# AVR.net
KiCad netlist of a schematic drawn in Altium Designer
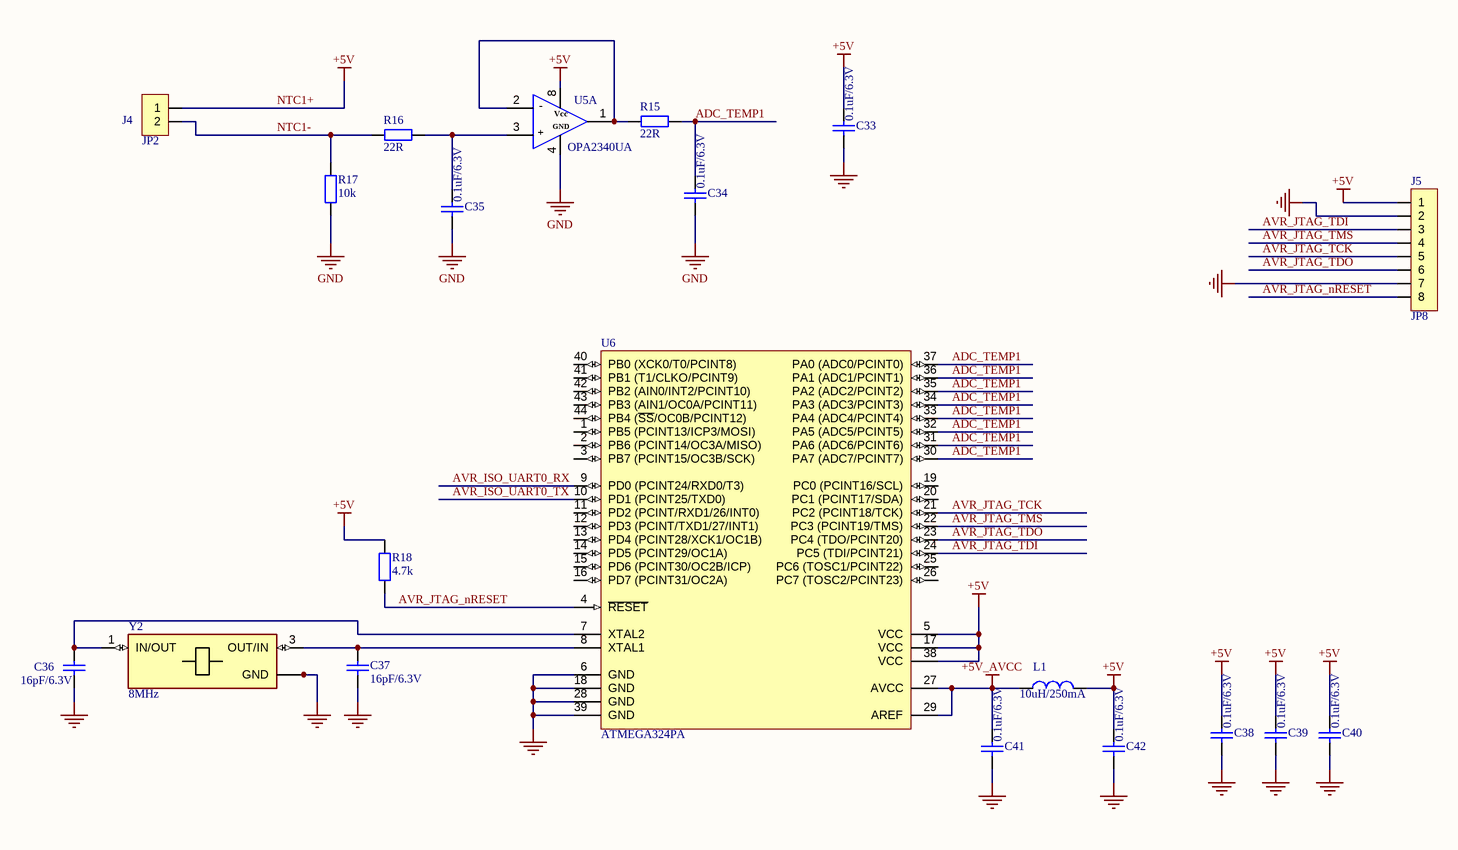
[diagram p0: AVR.SchDoc]

(export (version "E")
  (design (tool "Eeschema 10.0.6"))
  (components
    (comp (ref "C33")
      (value "0.1uF/6.3V")
      (footprint "CAP_C_1608X80")
      (description "CAPC")
      (libsource (lib "Altium_Lib_by_KhueNguyenCreator") (part "Tu 0402 33nF 10V"))
    )
    (comp (ref "C34")
      (value "0.1uF/6.3V")
      (footprint "CAP_C_1608X80")
      (description "CAPC")
      (libsource (lib "Altium_Lib_by_KhueNguyenCreator") (part "Tu 0402 33nF 10V"))
    )
    (comp (ref "C35")
      (value "0.1uF/6.3V")
      (footprint "CAP_C_1608X80")
      (description "CAPC")
      (libsource (lib "Altium_Lib_by_KhueNguyenCreator") (part "Tu 0402 33nF 10V"))
    )
    (comp (ref "C36")
      (value "16pF/6.3V")
      (footprint "CAP_C_1608X80")
      (description "CAPC")
      (libsource (lib "Altium_Lib_by_KhueNguyenCreator") (part "Tu 0402 33nF 10V"))
    )
    (comp (ref "C37")
      (value "16pF/6.3V")
      (footprint "CAP_C_1608X80")
      (description "CAPC")
      (libsource (lib "Altium_Lib_by_KhueNguyenCreator") (part "Tu 0402 33nF 10V"))
    )
    (comp (ref "C38")
      (value "0.1uF/6.3V")
      (footprint "CAP_C_1608X80")
      (description "CAPC")
      (libsource (lib "Altium_Lib_by_KhueNguyenCreator") (part "Tu 0402 33nF 10V"))
    )
    (comp (ref "C39")
      (value "0.1uF/6.3V")
      (footprint "CAP_C_1608X80")
      (description "CAPC")
      (libsource (lib "Altium_Lib_by_KhueNguyenCreator") (part "Tu 0402 33nF 10V"))
    )
    (comp (ref "C40")
      (value "0.1uF/6.3V")
      (footprint "CAP_C_1608X80")
      (description "CAPC")
      (libsource (lib "Altium_Lib_by_KhueNguyenCreator") (part "Tu 0402 33nF 10V"))
    )
    (comp (ref "C41")
      (value "0.1uF/6.3V")
      (footprint "CAP_C_1608X80")
      (description "CAPC")
      (libsource (lib "Altium_Lib_by_KhueNguyenCreator") (part "Tu 0402 33nF 10V"))
    )
    (comp (ref "C42")
      (value "0.1uF/6.3V")
      (footprint "CAP_C_1608X80")
      (description "CAPC")
      (libsource (lib "Altium_Lib_by_KhueNguyenCreator") (part "Tu 0402 33nF 10V"))
    )
    (comp (ref "J4")
      (value "JP2")
      (footprint "JP2-D1T")
      (description "WR-PHD 2.54 mm Angled Socket Header")
      (fields
        (field (name "MANUFACTURER") "Würth Elektronik eiSos GmbH")
        (field (name "PARTNO") "613002143121")
        (field (name "CREATED BY") "Karrer Zheng")
      )
      (libsource (lib "TechMT.VN_Lib") (part "JP2"))
    )
    (comp (ref "J5") (value "JP8") (footprint "JP8-C1T") (libsource (lib "obc_ver2") (part "JP8")))
    (comp (ref "L1")
      (value "10uH/250mA")
      (footprint "RES_C_1608X60")
      (fields
        (field (name "PARTNO") "78477010")
        (field (name "MANUFACTURER") "Wurth Elektronik")
        (field (name "CREATED BY") "Baojun Chen")
      )
      (libsource (lib "Sang_library") (part "L-SMD-1"))
    )
    (comp (ref "R15")
      (value "22R")
      (footprint "RES_C_1608X60")
      (description "RES")
      (libsource (lib "Altium_Lib_by_KhueNguyenCreator") (part "Tro 0603 1% 10k"))
    )
    (comp (ref "R16")
      (value "22R")
      (footprint "RES_C_1608X60")
      (description "RES")
      (libsource (lib "Altium_Lib_by_KhueNguyenCreator") (part "Tro 0603 1% 10k"))
    )
    (comp (ref "R17")
      (value "10k")
      (footprint "RES_C_1608X60")
      (description "RES")
      (libsource (lib "Altium_Lib_by_KhueNguyenCreator") (part "Tro 0603 1% 10k"))
    )
    (comp (ref "R18")
      (value "4.7k")
      (footprint "RES_C_1608X60")
      (description "RES")
      (libsource (lib "Altium_Lib_by_KhueNguyenCreator") (part "Tro 0603 1% 10k"))
    )
    (comp (ref "U5")
      (value "OPA2340UA")
      (footprint "SOIC127P602X173-8N")
      (libsource (lib "Sang_library") (part "OPA2340UA/2K5"))
    )
    (comp (ref "U6")
      (value "ATMEGA324PA")
      (footprint "QFP80P1200X1200X120-44")
      (libsource (lib "AUSB") (part "MCU_ATMEGA324PA"))
    )
    (comp (ref "Y2")
      (value "8MHz")
      (footprint "XTAL_ECS-250-12-33Q-JES-TR")
      (description "25 MHz Â±20ppm Crystal 12pF 40 Ohms 4-SMD, No Lead")
      (fields (field (name "MF") "ECS Inc.") (field (name "MP") "ECS-250-12-33Q-JES-TR"))
      (libsource (lib "ECS-250-12-33Q-JES-TR") (part "ECS-250-12-33Q-JES-TR"))
    )
  )
  (nets
    (net (code "1") (name "+5V") (class "Default")
      (node (ref "C33") (pin "1") (pinfunction "1_1") (pintype "passive"))
      (node (ref "C38") (pin "1") (pinfunction "1_1") (pintype "passive"))
      (node (ref "C39") (pin "1") (pinfunction "1_1") (pintype "passive"))
      (node (ref "C40") (pin "1") (pinfunction "1_1") (pintype "passive"))
      (node (ref "C42") (pin "1") (pinfunction "1_1") (pintype "passive"))
      (node (ref "J4") (pin "1") (pinfunction "1_1") (pintype "passive"))
      (node (ref "J5") (pin "1") (pinfunction "1_1") (pintype "passive"))
      (node (ref "L1") (pin "2") (pinfunction "2_2") (pintype "passive"))
      (node (ref "R18") (pin "2") (pinfunction "2_2") (pintype "passive"))
      (node (ref "U5") (pin "8") (pinfunction "8_8") (pintype "passive"))
      (node (ref "U6") (pin "17") (pinfunction "VCC_17") (pintype "power_in"))
      (node (ref "U6") (pin "38") (pinfunction "VCC_38") (pintype "power_in"))
      (node (ref "U6") (pin "5") (pinfunction "VCC_5") (pintype "power_in"))
    )
    (net (code "2") (name "+5V_AVCC") (class "Default")
      (node (ref "C41") (pin "1") (pinfunction "1_1") (pintype "passive"))
      (node (ref "L1") (pin "1") (pinfunction "1_1") (pintype "passive"))
      (node (ref "U6") (pin "27") (pinfunction "AVCC_27") (pintype "power_in"))
      (node (ref "U6") (pin "29") (pinfunction "AREF_29") (pintype "power_in"))
    )
    (net (code "3") (name "/ADC_TEMP1") (class "Default")
      (node (ref "C34") (pin "1") (pinfunction "1_1") (pintype "passive"))
      (node (ref "R15") (pin "1") (pinfunction "1_1") (pintype "passive"))
      (node (ref "U6") (pin "30") (pinfunction "PA7_(ADC7/PCINT7)_30") (pintype "bidirectional"))
      (node (ref "U6") (pin "31") (pinfunction "PA6_(ADC6/PCINT6)_31") (pintype "bidirectional"))
      (node (ref "U6") (pin "32") (pinfunction "PA5_(ADC5/PCINT5)_32") (pintype "bidirectional"))
      (node (ref "U6") (pin "33") (pinfunction "PA4_(ADC4/PCINT4)_33") (pintype "bidirectional"))
      (node (ref "U6") (pin "34") (pinfunction "PA3_(ADC3/PCINT3)_34") (pintype "bidirectional"))
      (node (ref "U6") (pin "35") (pinfunction "PA2_(ADC2/PCINT2)_35") (pintype "bidirectional"))
      (node (ref "U6") (pin "36") (pinfunction "PA1_(ADC1/PCINT1)_36") (pintype "bidirectional"))
      (node (ref "U6") (pin "37") (pinfunction "PA0_(ADC0/PCINT0)_37") (pintype "bidirectional"))
    )
    (net (code "4") (name "/AVR_ISO_UART0_RX") (class "Default")
      (node (ref "U6") (pin "9") (pinfunction "PD0_(PCINT24/RXD0/T3)_9") (pintype "bidirectional"))
    )
    (net (code "5") (name "/AVR_ISO_UART0_TX") (class "Default")
      (node (ref "U6") (pin "10") (pinfunction "PD1_(PCINT25/TXD0)_10") (pintype "bidirectional"))
    )
    (net (code "6") (name "/AVR_JTAG_TCK") (class "Default")
      (node (ref "J5") (pin "5") (pinfunction "5_5") (pintype "passive"))
      (node (ref "U6") (pin "21") (pinfunction "PC2_(PCINT18/TCK)_21") (pintype "bidirectional"))
    )
    (net (code "7") (name "/AVR_JTAG_TDI") (class "Default")
      (node (ref "J5") (pin "3") (pinfunction "3_3") (pintype "passive"))
      (node (ref "U6") (pin "24") (pinfunction "PC5_(TDI/PCINT21)_24") (pintype "bidirectional"))
    )
    (net (code "8") (name "/AVR_JTAG_TDO") (class "Default")
      (node (ref "J5") (pin "6") (pinfunction "6_6") (pintype "passive"))
      (node (ref "U6") (pin "23") (pinfunction "PC4_(TDO/PCINT20)_23") (pintype "bidirectional"))
    )
    (net (code "9") (name "/AVR_JTAG_TMS") (class "Default")
      (node (ref "J5") (pin "4") (pinfunction "4_4") (pintype "passive"))
      (node (ref "U6") (pin "22") (pinfunction "PC3_(PCINT19/TMS)_22") (pintype "bidirectional"))
    )
    (net (code "10") (name "/AVR_JTAG_nRESET") (class "Default")
      (node (ref "J5") (pin "8") (pinfunction "8_8") (pintype "passive"))
      (node (ref "R18") (pin "1") (pinfunction "1_1") (pintype "passive"))
      (node (ref "U6") (pin "4") (pinfunction "~{RESET}_4") (pintype "input"))
    )
    (net (code "11") (name "/NTC1-") (class "Default")
      (node (ref "J4") (pin "2") (pinfunction "2_2") (pintype "passive"))
      (node (ref "R16") (pin "2") (pinfunction "2_2") (pintype "passive"))
      (node (ref "R17") (pin "1") (pinfunction "1_1") (pintype "passive"))
    )
    (net (code "12") (name "GND") (class "Default")
      (node (ref "C33") (pin "2") (pinfunction "2_2") (pintype "passive"))
      (node (ref "C34") (pin "2") (pinfunction "2_2") (pintype "passive"))
      (node (ref "C35") (pin "2") (pinfunction "2_2") (pintype "passive"))
      (node (ref "C36") (pin "1") (pinfunction "1_1") (pintype "passive"))
      (node (ref "C37") (pin "1") (pinfunction "1_1") (pintype "passive"))
      (node (ref "C38") (pin "2") (pinfunction "2_2") (pintype "passive"))
      (node (ref "C39") (pin "2") (pinfunction "2_2") (pintype "passive"))
      (node (ref "C40") (pin "2") (pinfunction "2_2") (pintype "passive"))
      (node (ref "C41") (pin "2") (pinfunction "2_2") (pintype "passive"))
      (node (ref "C42") (pin "2") (pinfunction "2_2") (pintype "passive"))
      (node (ref "J5") (pin "2") (pinfunction "2_2") (pintype "passive"))
      (node (ref "J5") (pin "7") (pinfunction "7_7") (pintype "passive"))
      (node (ref "R17") (pin "2") (pinfunction "2_2") (pintype "passive"))
      (node (ref "U5") (pin "4") (pinfunction "4_4") (pintype "passive"))
      (node (ref "U6") (pin "18") (pinfunction "GND_18") (pintype "power_in"))
      (node (ref "U6") (pin "28") (pinfunction "GND_28") (pintype "power_in"))
      (node (ref "U6") (pin "39") (pinfunction "GND_39") (pintype "power_in"))
      (node (ref "U6") (pin "6") (pinfunction "GND_6") (pintype "power_in"))
      (node (ref "Y2") (pin "2") (pinfunction "GND_2") (pintype "power_in"))
      (node (ref "Y2") (pin "4") (pinfunction "GND_4") (pintype "power_in"))
    )
    (net (code "13") (name "Net-(C35-Pad1)") (class "Default")
      (node (ref "C35") (pin "1") (pinfunction "1_1") (pintype "passive"))
      (node (ref "R16") (pin "1") (pinfunction "1_1") (pintype "passive"))
      (node (ref "U5") (pin "3") (pinfunction "3_3") (pintype "passive"))
    )
    (net (code "14") (name "Net-(R15-Pad2)") (class "Default")
      (node (ref "R15") (pin "2") (pinfunction "2_2") (pintype "passive"))
      (node (ref "U5") (pin "1") (pinfunction "1_1") (pintype "passive"))
      (node (ref "U5") (pin "2") (pinfunction "2_2") (pintype "passive"))
    )
    (net (code "15") (name "Net-(U6-XTAL1)") (class "Default")
      (node (ref "C37") (pin "2") (pinfunction "2_2") (pintype "passive"))
      (node (ref "U6") (pin "8") (pinfunction "XTAL1_8") (pintype "passive"))
      (node (ref "Y2") (pin "3") (pinfunction "OUT/IN_3") (pintype "bidirectional"))
    )
    (net (code "16") (name "Net-(U6-XTAL2)") (class "Default")
      (node (ref "C36") (pin "2") (pinfunction "2_2") (pintype "passive"))
      (node (ref "U6") (pin "7") (pinfunction "XTAL2_7") (pintype "passive"))
      (node (ref "Y2") (pin "1") (pinfunction "IN/OUT_1") (pintype "bidirectional"))
    )
    (net (code "17") (name "unconnected-(U6-PB0_(XCK0{slash}T0{slash}PCINT8)-Pad40)") (class "Default")
      (node (ref "U6") (pin "40") (pinfunction "PB0_(XCK0/T0/PCINT8)_40") (pintype "bidirectional"))
    )
    (net (code "18") (name "unconnected-(U6-PB1_(T1{slash}CLKO{slash}PCINT9)-Pad41)") (class "Default")
      (node (ref "U6") (pin "41") (pinfunction "PB1_(T1/CLKO/PCINT9)_41") (pintype "bidirectional"))
    )
    (net (code "19") (name "unconnected-(U6-PB2_(AIN0{slash}INT2{slash}PCINT10)-Pad42)") (class "Default")
      (node (ref "U6") (pin "42") (pinfunction "PB2_(AIN0/INT2/PCINT10)_42") (pintype "bidirectional"))
    )
    (net (code "20") (name "unconnected-(U6-PB3_(AIN1{slash}OC0A{slash}PCINT11)-Pad43)") (class "Default")
      (node (ref "U6") (pin "43") (pinfunction "PB3_(AIN1/OC0A/PCINT11)_43") (pintype "bidirectional"))
    )
    (net (code "21") (name "unconnected-(U6-PB4_(~{SS}{slash}OC0B{slash}PCINT12)-Pad44)") (class "Default")
      (node (ref "U6") (pin "44") (pinfunction "PB4_(~{SS}/OC0B/PCINT12)_44") (pintype "bidirectional"))
    )
    (net (code "22") (name "unconnected-(U6-PB5_(PCINT13{slash}ICP3{slash}MOSI)-Pad1)") (class "Default")
      (node (ref "U6") (pin "1") (pinfunction "PB5_(PCINT13/ICP3/MOSI)_1") (pintype "bidirectional"))
    )
    (net (code "23") (name "unconnected-(U6-PB6_(PCINT14{slash}OC3A{slash}MISO)-Pad2)") (class "Default")
      (node (ref "U6") (pin "2") (pinfunction "PB6_(PCINT14/OC3A/MISO)_2") (pintype "bidirectional"))
    )
    (net (code "24") (name "unconnected-(U6-PB7_(PCINT15{slash}OC3B{slash}SCK)-Pad3)") (class "Default")
      (node (ref "U6") (pin "3") (pinfunction "PB7_(PCINT15/OC3B/SCK)_3") (pintype "bidirectional"))
    )
    (net (code "25") (name "unconnected-(U6-PC0_(PCINT16{slash}SCL)-Pad19)") (class "Default")
      (node (ref "U6") (pin "19") (pinfunction "PC0_(PCINT16/SCL)_19") (pintype "bidirectional"))
    )
    (net (code "26") (name "unconnected-(U6-PC1_(PCINT17{slash}SDA)-Pad20)") (class "Default")
      (node (ref "U6") (pin "20") (pinfunction "PC1_(PCINT17/SDA)_20") (pintype "bidirectional"))
    )
    (net (code "27") (name "unconnected-(U6-PC6_(TOSC1{slash}PCINT22)-Pad25)") (class "Default")
      (node (ref "U6") (pin "25") (pinfunction "PC6_(TOSC1/PCINT22)_25") (pintype "bidirectional"))
    )
    (net (code "28") (name "unconnected-(U6-PC7_(TOSC2{slash}PCINT23)-Pad26)") (class "Default")
      (node (ref "U6") (pin "26") (pinfunction "PC7_(TOSC2/PCINT23)_26") (pintype "bidirectional"))
    )
    (net (code "29") (name "unconnected-(U6-PD2_(PCINT{slash}RXD1{slash}26{slash}INT0)-Pad11)") (class "Default")
      (node (ref "U6") (pin "11") (pinfunction "PD2_(PCINT/RXD1/26/INT0)_11") (pintype "bidirectional"))
    )
    (net (code "30") (name "unconnected-(U6-PD3_(PCINT{slash}TXD1{slash}27{slash}INT1)-Pad12)") (class "Default")
      (node (ref "U6") (pin "12") (pinfunction "PD3_(PCINT/TXD1/27/INT1)_12") (pintype "bidirectional"))
    )
    (net (code "31") (name "unconnected-(U6-PD4_(PCINT28{slash}XCK1{slash}OC1B)-Pad13)") (class "Default")
      (node (ref "U6") (pin "13") (pinfunction "PD4_(PCINT28/XCK1/OC1B)_13") (pintype "bidirectional"))
    )
    (net (code "32") (name "unconnected-(U6-PD5_(PCINT29{slash}OC1A)-Pad14)") (class "Default")
      (node (ref "U6") (pin "14") (pinfunction "PD5_(PCINT29/OC1A)_14") (pintype "bidirectional"))
    )
    (net (code "33") (name "unconnected-(U6-PD6_(PCINT30{slash}OC2B{slash}ICP)-Pad15)") (class "Default")
      (node (ref "U6") (pin "15") (pinfunction "PD6_(PCINT30/OC2B/ICP)_15") (pintype "bidirectional"))
    )
    (net (code "34") (name "unconnected-(U6-PD7_(PCINT31{slash}OC2A)-Pad16)") (class "Default")
      (node (ref "U6") (pin "16") (pinfunction "PD7_(PCINT31/OC2A)_16") (pintype "bidirectional"))
    )
  )
)
